# Sheet1.net
KiCad netlist of a schematic drawn in Altium Designer
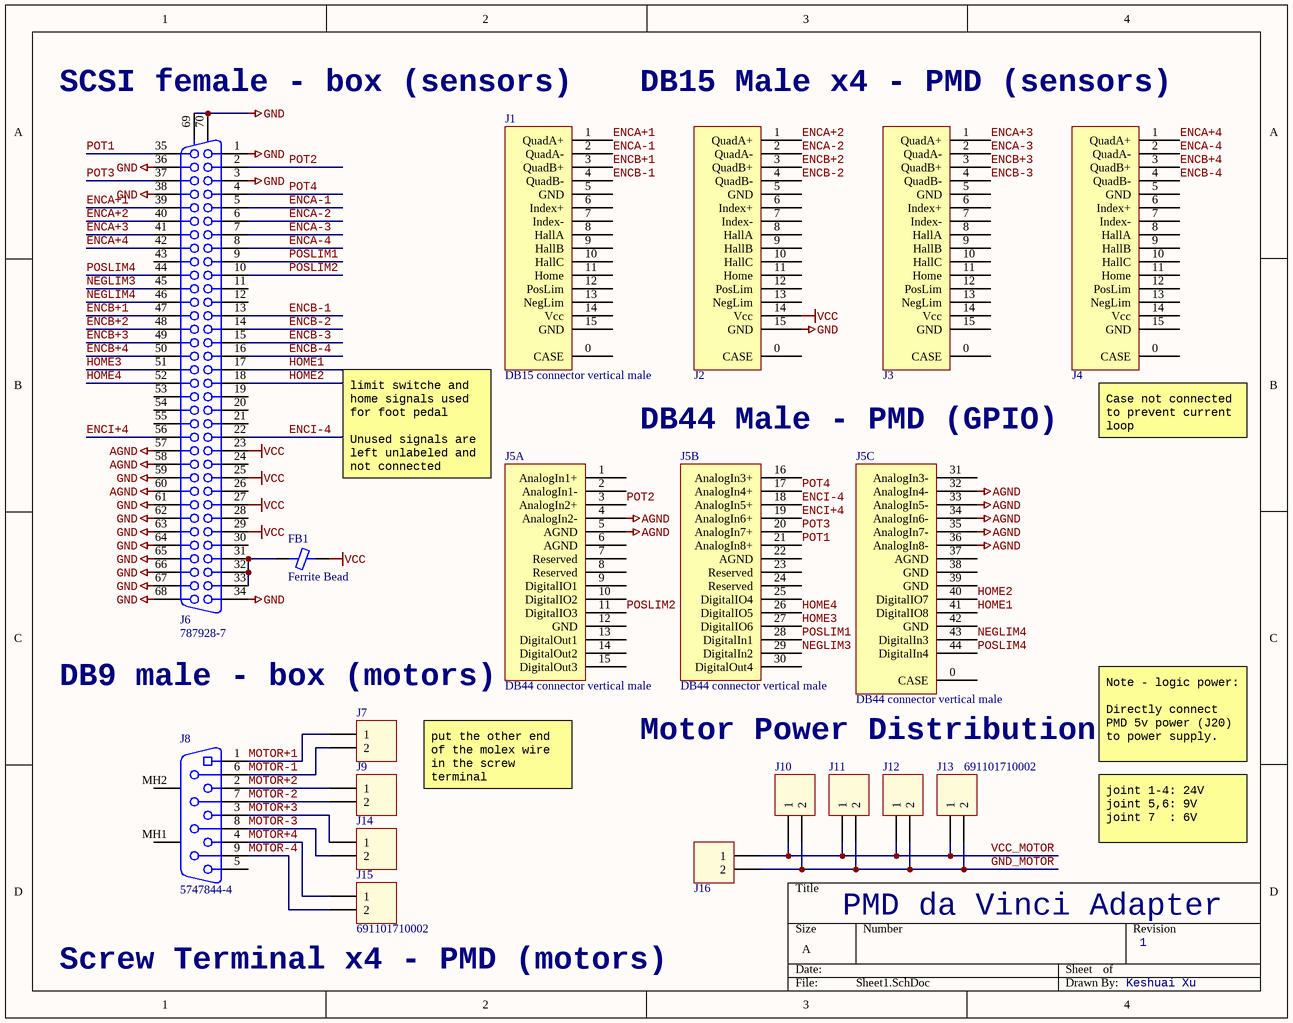
[diagram p0: Sheet1.SchDoc]

(export (version "E")
  (design (tool "Eeschema 10.0.6"))
  (components
    (comp (ref "FB1")
      (value "Ferrite Bead")
      (footprint "IND_0603")
      (description "SMT Ferrite Chip")
      (libsource (lib "Passives") (part "Ferrite Chip"))
    )
    (comp (ref "J1")
      (value "DB15 connector vertical male")
      (footprint "10090928-P154XLF")
      (libsource (lib "pmd_davinci_adapter") (part "PMD-sensor"))
    )
    (comp (ref "J2")
      (value "DB15 connector vertical male")
      (footprint "10090928-P154XLF")
      (libsource (lib "pmd_davinci_adapter") (part "PMD-sensor"))
    )
    (comp (ref "J3")
      (value "DB15 connector vertical male")
      (footprint "10090928-P154XLF")
      (libsource (lib "pmd_davinci_adapter") (part "PMD-sensor"))
    )
    (comp (ref "J4")
      (value "DB15 connector vertical male")
      (footprint "10090928-P154XLF")
      (libsource (lib "pmd_davinci_adapter") (part "PMD-sensor"))
    )
    (comp (ref "J5")
      (value "DB44 connector vertical male")
      (footprint "10090928-P444XLF")
      (libsource (lib "pmd_davinci_adapter") (part "PMD-GPIO"))
    )
    (comp (ref "J6")
      (value "787928-7")
      (footprint "787928-7")
      (description "Receptacle Assembly, Shielded, Right Angle, AMPLIMITE")
      (fields (field (name "PUBLISHER") "Altium Limited"))
      (libsource (lib "pmd_davinci_adapter") (part "787928-7"))
    )
    (comp (ref "J7")
      (value "691101710002")
      (footprint "691101710002")
      (description "WR-TBL Serie 101 - 5.00 mm Horizontal Entry Modular, 02p")
      (fields (field (name "PUBLISHER") "Wurth Elektronik"))
      (libsource (lib "ALTIUM-TBL_5_00_THR_5027_HORIZONTAL_ENTRY_MODULAR_W_PRESSURE_CLAMP_69150271000X-rev17a") (part "691101710002"))
    )
    (comp (ref "J8")
      (value "5747844-4")
      (footprint "TE-5747844-4_V")
      (fields (field (name "MANUFACTURER") "TE Connectivity"))
      (libsource (lib "Altium Content Vault") (part "CN-2S-2F-D9"))
    )
    (comp (ref "J9")
      (value "691101710002")
      (footprint "691101710002")
      (description "WR-TBL Serie 101 - 5.00 mm Horizontal Entry Modular, 02p")
      (fields (field (name "PUBLISHER") "Wurth Elektronik"))
      (libsource (lib "ALTIUM-TBL_5_00_THR_5027_HORIZONTAL_ENTRY_MODULAR_W_PRESSURE_CLAMP_69150271000X-rev17a") (part "691101710002"))
    )
    (comp (ref "J10")
      (value "691101710002")
      (footprint "691101710002")
      (description "WR-TBL Serie 101 - 5.00 mm Horizontal Entry Modular, 02p")
      (fields (field (name "PUBLISHER") "Wurth Elektronik"))
      (libsource (lib "") (part "691101710002_1"))
    )
    (comp (ref "J11")
      (value "691101710002")
      (footprint "691101710002")
      (description "WR-TBL Serie 101 - 5.00 mm Horizontal Entry Modular, 02p")
      (fields (field (name "PUBLISHER") "Wurth Elektronik"))
      (libsource (lib "") (part "691101710002_1"))
    )
    (comp (ref "J12")
      (value "691101710002")
      (footprint "691101710002")
      (description "WR-TBL Serie 101 - 5.00 mm Horizontal Entry Modular, 02p")
      (fields (field (name "PUBLISHER") "Wurth Elektronik"))
      (libsource (lib "") (part "691101710002_1"))
    )
    (comp (ref "J13")
      (value "691101710002")
      (footprint "691101710002")
      (description "WR-TBL Serie 101 - 5.00 mm Horizontal Entry Modular, 02p")
      (fields (field (name "PUBLISHER") "Wurth Elektronik"))
      (libsource (lib "") (part "691101710002_1"))
    )
    (comp (ref "J14")
      (value "691101710002")
      (footprint "691101710002")
      (description "WR-TBL Serie 101 - 5.00 mm Horizontal Entry Modular, 02p")
      (fields (field (name "PUBLISHER") "Wurth Elektronik"))
      (libsource (lib "ALTIUM-TBL_5_00_THR_5027_HORIZONTAL_ENTRY_MODULAR_W_PRESSURE_CLAMP_69150271000X-rev17a") (part "691101710002"))
    )
    (comp (ref "J15")
      (value "691101710002")
      (footprint "691101710002")
      (description "WR-TBL Serie 101 - 5.00 mm Horizontal Entry Modular, 02p")
      (fields (field (name "PUBLISHER") "Wurth Elektronik"))
      (libsource (lib "ALTIUM-TBL_5_00_THR_5027_HORIZONTAL_ENTRY_MODULAR_W_PRESSURE_CLAMP_69150271000X-rev17a") (part "691101710002"))
    )
    (comp (ref "J16")
      (value "691101710002")
      (footprint "691101710002")
      (description "WR-TBL Serie 101 - 5.00 mm Horizontal Entry Modular, 02p")
      (fields (field (name "PUBLISHER") "Wurth Elektronik"))
      (libsource (lib "") (part "691101710002_2"))
    )
  )
  (nets
    (net (code "1") (name "/ENCA+1") (class "Default")
      (node (ref "J1") (pin "1") (pinfunction "QuadA+_1") (pintype "passive"))
      (node (ref "J6") (pin "39") (pinfunction "39_39") (pintype "passive"))
    )
    (net (code "2") (name "/ENCA+2") (class "Default")
      (node (ref "J2") (pin "1") (pinfunction "QuadA+_1") (pintype "passive"))
      (node (ref "J6") (pin "40") (pinfunction "40_40") (pintype "passive"))
    )
    (net (code "3") (name "/ENCA+3") (class "Default")
      (node (ref "J3") (pin "1") (pinfunction "QuadA+_1") (pintype "passive"))
      (node (ref "J6") (pin "41") (pinfunction "41_41") (pintype "passive"))
    )
    (net (code "4") (name "/ENCA+4") (class "Default")
      (node (ref "J4") (pin "1") (pinfunction "QuadA+_1") (pintype "passive"))
      (node (ref "J6") (pin "42") (pinfunction "42_42") (pintype "passive"))
    )
    (net (code "5") (name "/ENCA-1") (class "Default")
      (node (ref "J1") (pin "2") (pinfunction "QuadA-_2") (pintype "passive"))
      (node (ref "J6") (pin "5") (pinfunction "5_5") (pintype "passive"))
    )
    (net (code "6") (name "/ENCA-2") (class "Default")
      (node (ref "J2") (pin "2") (pinfunction "QuadA-_2") (pintype "passive"))
      (node (ref "J6") (pin "6") (pinfunction "6_6") (pintype "passive"))
    )
    (net (code "7") (name "/ENCA-3") (class "Default")
      (node (ref "J3") (pin "2") (pinfunction "QuadA-_2") (pintype "passive"))
      (node (ref "J6") (pin "7") (pinfunction "7_7") (pintype "passive"))
    )
    (net (code "8") (name "/ENCA-4") (class "Default")
      (node (ref "J4") (pin "2") (pinfunction "QuadA-_2") (pintype "passive"))
      (node (ref "J6") (pin "8") (pinfunction "8_8") (pintype "passive"))
    )
    (net (code "9") (name "/ENCB+1") (class "Default")
      (node (ref "J1") (pin "3") (pinfunction "QuadB+_3") (pintype "passive"))
      (node (ref "J6") (pin "47") (pinfunction "47_47") (pintype "passive"))
    )
    (net (code "10") (name "/ENCB+2") (class "Default")
      (node (ref "J2") (pin "3") (pinfunction "QuadB+_3") (pintype "passive"))
      (node (ref "J6") (pin "48") (pinfunction "48_48") (pintype "passive"))
    )
    (net (code "11") (name "/ENCB+3") (class "Default")
      (node (ref "J3") (pin "3") (pinfunction "QuadB+_3") (pintype "passive"))
      (node (ref "J6") (pin "49") (pinfunction "49_49") (pintype "passive"))
    )
    (net (code "12") (name "/ENCB+4") (class "Default")
      (node (ref "J4") (pin "3") (pinfunction "QuadB+_3") (pintype "passive"))
      (node (ref "J6") (pin "50") (pinfunction "50_50") (pintype "passive"))
    )
    (net (code "13") (name "/ENCB-1") (class "Default")
      (node (ref "J1") (pin "4") (pinfunction "QuadB-_4") (pintype "passive"))
      (node (ref "J6") (pin "13") (pinfunction "13_13") (pintype "passive"))
    )
    (net (code "14") (name "/ENCB-2") (class "Default")
      (node (ref "J2") (pin "4") (pinfunction "QuadB-_4") (pintype "passive"))
      (node (ref "J6") (pin "14") (pinfunction "14_14") (pintype "passive"))
    )
    (net (code "15") (name "/ENCB-3") (class "Default")
      (node (ref "J3") (pin "4") (pinfunction "QuadB-_4") (pintype "passive"))
      (node (ref "J6") (pin "15") (pinfunction "15_15") (pintype "passive"))
    )
    (net (code "16") (name "/ENCB-4") (class "Default")
      (node (ref "J4") (pin "4") (pinfunction "QuadB-_4") (pintype "passive"))
      (node (ref "J6") (pin "16") (pinfunction "16_16") (pintype "passive"))
    )
    (net (code "17") (name "/ENCI+4") (class "Default")
      (node (ref "J5") (pin "19") (pinfunction "AnalogIn6+_19") (pintype "passive"))
      (node (ref "J6") (pin "56") (pinfunction "56_56") (pintype "passive"))
    )
    (net (code "18") (name "/ENCI-4") (class "Default")
      (node (ref "J5") (pin "18") (pinfunction "AnalogIn5+_18") (pintype "passive"))
      (node (ref "J6") (pin "22") (pinfunction "22_22") (pintype "passive"))
    )
    (net (code "19") (name "/GND_MOTOR") (class "Default")
      (node (ref "J10") (pin "2") (pinfunction "2_2") (pintype "passive"))
      (node (ref "J11") (pin "2") (pinfunction "2_2") (pintype "passive"))
      (node (ref "J12") (pin "2") (pinfunction "2_2") (pintype "passive"))
      (node (ref "J13") (pin "2") (pinfunction "2_2") (pintype "passive"))
      (node (ref "J16") (pin "2") (pinfunction "2_2") (pintype "passive"))
    )
    (net (code "20") (name "/HOME1") (class "Default")
      (node (ref "J5") (pin "41") (pinfunction "DigitalIO8_41") (pintype "passive"))
      (node (ref "J6") (pin "17") (pinfunction "17_17") (pintype "passive"))
    )
    (net (code "21") (name "/HOME2") (class "Default")
      (node (ref "J5") (pin "40") (pinfunction "DigitalIO7_40") (pintype "passive"))
      (node (ref "J6") (pin "18") (pinfunction "18_18") (pintype "passive"))
    )
    (net (code "22") (name "/HOME3") (class "Default")
      (node (ref "J5") (pin "27") (pinfunction "DigitalIO6_27") (pintype "passive"))
      (node (ref "J6") (pin "51") (pinfunction "51_51") (pintype "passive"))
    )
    (net (code "23") (name "/HOME4") (class "Default")
      (node (ref "J5") (pin "26") (pinfunction "DigitalIO5_26") (pintype "passive"))
      (node (ref "J6") (pin "52") (pinfunction "52_52") (pintype "passive"))
    )
    (net (code "24") (name "/MOTOR+1") (class "Default")
      (node (ref "J7") (pin "1") (pinfunction "1_1") (pintype "passive"))
      (node (ref "J8") (pin "1") (pinfunction "1_1") (pintype "passive"))
    )
    (net (code "25") (name "/MOTOR+2") (class "Default")
      (node (ref "J8") (pin "2") (pinfunction "2_2") (pintype "passive"))
      (node (ref "J9") (pin "1") (pinfunction "1_1") (pintype "passive"))
    )
    (net (code "26") (name "/MOTOR+3") (class "Default")
      (node (ref "J14") (pin "1") (pinfunction "1_1") (pintype "passive"))
      (node (ref "J8") (pin "3") (pinfunction "3_3") (pintype "passive"))
    )
    (net (code "27") (name "/MOTOR+4") (class "Default")
      (node (ref "J15") (pin "1") (pinfunction "1_1") (pintype "passive"))
      (node (ref "J8") (pin "4") (pinfunction "4_4") (pintype "passive"))
    )
    (net (code "28") (name "/MOTOR-1") (class "Default")
      (node (ref "J7") (pin "2") (pinfunction "2_2") (pintype "passive"))
      (node (ref "J8") (pin "6") (pinfunction "6_6") (pintype "passive"))
    )
    (net (code "29") (name "/MOTOR-2") (class "Default")
      (node (ref "J8") (pin "7") (pinfunction "7_7") (pintype "passive"))
      (node (ref "J9") (pin "2") (pinfunction "2_2") (pintype "passive"))
    )
    (net (code "30") (name "/MOTOR-3") (class "Default")
      (node (ref "J14") (pin "2") (pinfunction "2_2") (pintype "passive"))
      (node (ref "J8") (pin "8") (pinfunction "8_8") (pintype "passive"))
    )
    (net (code "31") (name "/MOTOR-4") (class "Default")
      (node (ref "J15") (pin "2") (pinfunction "2_2") (pintype "passive"))
      (node (ref "J8") (pin "9") (pinfunction "9_9") (pintype "passive"))
    )
    (net (code "32") (name "/NEGLIM3") (class "Default")
      (node (ref "J5") (pin "29") (pinfunction "DigitalIn2_29") (pintype "passive"))
      (node (ref "J6") (pin "45") (pinfunction "45_45") (pintype "passive"))
    )
    (net (code "33") (name "/NEGLIM4") (class "Default")
      (node (ref "J5") (pin "43") (pinfunction "DigitalIn3_43") (pintype "passive"))
      (node (ref "J6") (pin "46") (pinfunction "46_46") (pintype "passive"))
    )
    (net (code "34") (name "/POSLIM1") (class "Default")
      (node (ref "J5") (pin "28") (pinfunction "DigitalIn1_28") (pintype "passive"))
      (node (ref "J6") (pin "9") (pinfunction "9_9") (pintype "passive"))
    )
    (net (code "35") (name "/POSLIM2") (class "Default")
      (node (ref "J5") (pin "11") (pinfunction "DigitalIO3_11") (pintype "passive"))
      (node (ref "J6") (pin "10") (pinfunction "10_10") (pintype "passive"))
    )
    (net (code "36") (name "/POSLIM4") (class "Default")
      (node (ref "J5") (pin "44") (pinfunction "DigitalIn4_44") (pintype "passive"))
      (node (ref "J6") (pin "44") (pinfunction "44_44") (pintype "passive"))
    )
    (net (code "37") (name "/POT1") (class "Default")
      (node (ref "J5") (pin "21") (pinfunction "AnalogIn8+_21") (pintype "passive"))
      (node (ref "J6") (pin "35") (pinfunction "35_35") (pintype "passive"))
    )
    (net (code "38") (name "/POT2") (class "Default")
      (node (ref "J5") (pin "3") (pinfunction "AnalogIn2+_3") (pintype "passive"))
      (node (ref "J6") (pin "2") (pinfunction "2_2") (pintype "passive"))
    )
    (net (code "39") (name "/POT3") (class "Default")
      (node (ref "J5") (pin "20") (pinfunction "AnalogIn7+_20") (pintype "passive"))
      (node (ref "J6") (pin "37") (pinfunction "37_37") (pintype "passive"))
    )
    (net (code "40") (name "/POT4") (class "Default")
      (node (ref "J5") (pin "17") (pinfunction "AnalogIn4+_17") (pintype "passive"))
      (node (ref "J6") (pin "4") (pinfunction "4_4") (pintype "passive"))
    )
    (net (code "41") (name "/VCC_MOTOR") (class "Default")
      (node (ref "J10") (pin "1") (pinfunction "1_1") (pintype "passive"))
      (node (ref "J11") (pin "1") (pinfunction "1_1") (pintype "passive"))
      (node (ref "J12") (pin "1") (pinfunction "1_1") (pintype "passive"))
      (node (ref "J13") (pin "1") (pinfunction "1_1") (pintype "passive"))
      (node (ref "J16") (pin "1") (pinfunction "1_1") (pintype "passive"))
    )
    (net (code "42") (name "AGND") (class "Default")
      (node (ref "J5") (pin "32") (pinfunction "AnalogIn4-_32") (pintype "passive"))
      (node (ref "J5") (pin "33") (pinfunction "AnalogIn5-_33") (pintype "passive"))
      (node (ref "J5") (pin "34") (pinfunction "AnalogIn6-_34") (pintype "passive"))
      (node (ref "J5") (pin "35") (pinfunction "AnalogIn7-_35") (pintype "passive"))
      (node (ref "J5") (pin "36") (pinfunction "AnalogIn8-_36") (pintype "passive"))
      (node (ref "J5") (pin "4") (pinfunction "AnalogIn2-_4") (pintype "passive"))
      (node (ref "J5") (pin "5") (pinfunction "AGND_5") (pintype "passive"))
      (node (ref "J6") (pin "57") (pinfunction "57_57") (pintype "passive"))
      (node (ref "J6") (pin "58") (pinfunction "58_58") (pintype "passive"))
      (node (ref "J6") (pin "60") (pinfunction "60_60") (pintype "passive"))
    )
    (net (code "43") (name "GND") (class "Default")
      (node (ref "J2") (pin "15") (pinfunction "GND_15") (pintype "passive"))
      (node (ref "J6") (pin "1") (pinfunction "1_1") (pintype "passive"))
      (node (ref "J6") (pin "3") (pinfunction "3_3") (pintype "passive"))
      (node (ref "J6") (pin "34") (pinfunction "34_34") (pintype "passive"))
      (node (ref "J6") (pin "36") (pinfunction "36_36") (pintype "passive"))
      (node (ref "J6") (pin "38") (pinfunction "38_38") (pintype "passive"))
      (node (ref "J6") (pin "59") (pinfunction "59_59") (pintype "passive"))
      (node (ref "J6") (pin "61") (pinfunction "61_61") (pintype "passive"))
      (node (ref "J6") (pin "62") (pinfunction "62_62") (pintype "passive"))
      (node (ref "J6") (pin "63") (pinfunction "63_63") (pintype "passive"))
      (node (ref "J6") (pin "64") (pinfunction "64_64") (pintype "passive"))
      (node (ref "J6") (pin "65") (pinfunction "65_65") (pintype "passive"))
      (node (ref "J6") (pin "66") (pinfunction "66_66") (pintype "passive"))
      (node (ref "J6") (pin "67") (pinfunction "67_67") (pintype "passive"))
      (node (ref "J6") (pin "68") (pinfunction "68_68") (pintype "passive"))
      (node (ref "J6") (pin "69") (pinfunction "MH1_69") (pintype "passive"))
      (node (ref "J6") (pin "70") (pinfunction "MH2_70") (pintype "passive"))
    )
    (net (code "44") (name "Net-(FB1-Pad1)") (class "Default")
      (node (ref "FB1") (pin "1") (pinfunction "1_1") (pintype "passive"))
      (node (ref "J6") (pin "31") (pinfunction "31_31") (pintype "passive"))
      (node (ref "J6") (pin "32") (pinfunction "32_32") (pintype "passive"))
      (node (ref "J6") (pin "33") (pinfunction "33_33") (pintype "passive"))
    )
    (net (code "45") (name "VCC") (class "Default")
      (node (ref "FB1") (pin "2") (pinfunction "2_2") (pintype "passive"))
      (node (ref "J2") (pin "14") (pinfunction "Vcc_14") (pintype "passive"))
      (node (ref "J6") (pin "23") (pinfunction "23_23") (pintype "passive"))
      (node (ref "J6") (pin "25") (pinfunction "25_25") (pintype "passive"))
      (node (ref "J6") (pin "27") (pinfunction "27_27") (pintype "passive"))
      (node (ref "J6") (pin "29") (pinfunction "29_29") (pintype "passive"))
    )
    (net (code "46") (name "unconnected-(J1-CASE-Pad0)") (class "Default")
      (node (ref "J1") (pin "0") (pinfunction "CASE_0") (pintype "passive"))
    )
    (net (code "47") (name "unconnected-(J1-GND-Pad5)") (class "Default")
      (node (ref "J1") (pin "5") (pinfunction "GND_5") (pintype "passive"))
    )
    (net (code "48") (name "unconnected-(J1-GND-Pad15)") (class "Default")
      (node (ref "J1") (pin "15") (pinfunction "GND_15") (pintype "passive"))
    )
    (net (code "49") (name "unconnected-(J1-HallA-Pad8)") (class "Default")
      (node (ref "J1") (pin "8") (pinfunction "HallA_8") (pintype "passive"))
    )
    (net (code "50") (name "unconnected-(J1-HallB-Pad9)") (class "Default")
      (node (ref "J1") (pin "9") (pinfunction "HallB_9") (pintype "passive"))
    )
    (net (code "51") (name "unconnected-(J1-HallC-Pad10)") (class "Default")
      (node (ref "J1") (pin "10") (pinfunction "HallC_10") (pintype "passive"))
    )
    (net (code "52") (name "unconnected-(J1-Home-Pad11)") (class "Default")
      (node (ref "J1") (pin "11") (pinfunction "Home_11") (pintype "passive"))
    )
    (net (code "53") (name "unconnected-(J1-Index+-Pad6)") (class "Default")
      (node (ref "J1") (pin "6") (pinfunction "Index+_6") (pintype "passive"))
    )
    (net (code "54") (name "unconnected-(J1-Index--Pad7)") (class "Default")
      (node (ref "J1") (pin "7") (pinfunction "Index-_7") (pintype "passive"))
    )
    (net (code "55") (name "unconnected-(J1-NegLim-Pad13)") (class "Default")
      (node (ref "J1") (pin "13") (pinfunction "NegLim_13") (pintype "passive"))
    )
    (net (code "56") (name "unconnected-(J1-PosLim-Pad12)") (class "Default")
      (node (ref "J1") (pin "12") (pinfunction "PosLim_12") (pintype "passive"))
    )
    (net (code "57") (name "unconnected-(J1-Vcc-Pad14)") (class "Default")
      (node (ref "J1") (pin "14") (pinfunction "Vcc_14") (pintype "passive"))
    )
    (net (code "58") (name "unconnected-(J2-CASE-Pad0)") (class "Default")
      (node (ref "J2") (pin "0") (pinfunction "CASE_0") (pintype "passive"))
    )
    (net (code "59") (name "unconnected-(J2-GND-Pad5)") (class "Default")
      (node (ref "J2") (pin "5") (pinfunction "GND_5") (pintype "passive"))
    )
    (net (code "60") (name "unconnected-(J2-HallA-Pad8)") (class "Default")
      (node (ref "J2") (pin "8") (pinfunction "HallA_8") (pintype "passive"))
    )
    (net (code "61") (name "unconnected-(J2-HallB-Pad9)") (class "Default")
      (node (ref "J2") (pin "9") (pinfunction "HallB_9") (pintype "passive"))
    )
    (net (code "62") (name "unconnected-(J2-HallC-Pad10)") (class "Default")
      (node (ref "J2") (pin "10") (pinfunction "HallC_10") (pintype "passive"))
    )
    (net (code "63") (name "unconnected-(J2-Home-Pad11)") (class "Default")
      (node (ref "J2") (pin "11") (pinfunction "Home_11") (pintype "passive"))
    )
    (net (code "64") (name "unconnected-(J2-Index+-Pad6)") (class "Default")
      (node (ref "J2") (pin "6") (pinfunction "Index+_6") (pintype "passive"))
    )
    (net (code "65") (name "unconnected-(J2-Index--Pad7)") (class "Default")
      (node (ref "J2") (pin "7") (pinfunction "Index-_7") (pintype "passive"))
    )
    (net (code "66") (name "unconnected-(J2-NegLim-Pad13)") (class "Default")
      (node (ref "J2") (pin "13") (pinfunction "NegLim_13") (pintype "passive"))
    )
    (net (code "67") (name "unconnected-(J2-PosLim-Pad12)") (class "Default")
      (node (ref "J2") (pin "12") (pinfunction "PosLim_12") (pintype "passive"))
    )
    (net (code "68") (name "unconnected-(J3-CASE-Pad0)") (class "Default")
      (node (ref "J3") (pin "0") (pinfunction "CASE_0") (pintype "passive"))
    )
    (net (code "69") (name "unconnected-(J3-GND-Pad5)") (class "Default")
      (node (ref "J3") (pin "5") (pinfunction "GND_5") (pintype "passive"))
    )
    (net (code "70") (name "unconnected-(J3-GND-Pad15)") (class "Default")
      (node (ref "J3") (pin "15") (pinfunction "GND_15") (pintype "passive"))
    )
    (net (code "71") (name "unconnected-(J3-HallA-Pad8)") (class "Default")
      (node (ref "J3") (pin "8") (pinfunction "HallA_8") (pintype "passive"))
    )
    (net (code "72") (name "unconnected-(J3-HallB-Pad9)") (class "Default")
      (node (ref "J3") (pin "9") (pinfunction "HallB_9") (pintype "passive"))
    )
    (net (code "73") (name "unconnected-(J3-HallC-Pad10)") (class "Default")
      (node (ref "J3") (pin "10") (pinfunction "HallC_10") (pintype "passive"))
    )
    (net (code "74") (name "unconnected-(J3-Home-Pad11)") (class "Default")
      (node (ref "J3") (pin "11") (pinfunction "Home_11") (pintype "passive"))
    )
    (net (code "75") (name "unconnected-(J3-Index+-Pad6)") (class "Default")
      (node (ref "J3") (pin "6") (pinfunction "Index+_6") (pintype "passive"))
    )
    (net (code "76") (name "unconnected-(J3-Index--Pad7)") (class "Default")
      (node (ref "J3") (pin "7") (pinfunction "Index-_7") (pintype "passive"))
    )
    (net (code "77") (name "unconnected-(J3-NegLim-Pad13)") (class "Default")
      (node (ref "J3") (pin "13") (pinfunction "NegLim_13") (pintype "passive"))
    )
    (net (code "78") (name "unconnected-(J3-PosLim-Pad12)") (class "Default")
      (node (ref "J3") (pin "12") (pinfunction "PosLim_12") (pintype "passive"))
    )
    (net (code "79") (name "unconnected-(J3-Vcc-Pad14)") (class "Default")
      (node (ref "J3") (pin "14") (pinfunction "Vcc_14") (pintype "passive"))
    )
    (net (code "80") (name "unconnected-(J4-CASE-Pad0)") (class "Default")
      (node (ref "J4") (pin "0") (pinfunction "CASE_0") (pintype "passive"))
    )
    (net (code "81") (name "unconnected-(J4-GND-Pad5)") (class "Default")
      (node (ref "J4") (pin "5") (pinfunction "GND_5") (pintype "passive"))
    )
    (net (code "82") (name "unconnected-(J4-GND-Pad15)") (class "Default")
      (node (ref "J4") (pin "15") (pinfunction "GND_15") (pintype "passive"))
    )
    (net (code "83") (name "unconnected-(J4-HallA-Pad8)") (class "Default")
      (node (ref "J4") (pin "8") (pinfunction "HallA_8") (pintype "passive"))
    )
    (net (code "84") (name "unconnected-(J4-HallB-Pad9)") (class "Default")
      (node (ref "J4") (pin "9") (pinfunction "HallB_9") (pintype "passive"))
    )
    (net (code "85") (name "unconnected-(J4-HallC-Pad10)") (class "Default")
      (node (ref "J4") (pin "10") (pinfunction "HallC_10") (pintype "passive"))
    )
    (net (code "86") (name "unconnected-(J4-Home-Pad11)") (class "Default")
      (node (ref "J4") (pin "11") (pinfunction "Home_11") (pintype "passive"))
    )
    (net (code "87") (name "unconnected-(J4-Index+-Pad6)") (class "Default")
      (node (ref "J4") (pin "6") (pinfunction "Index+_6") (pintype "passive"))
    )
    (net (code "88") (name "unconnected-(J4-Index--Pad7)") (class "Default")
      (node (ref "J4") (pin "7") (pinfunction "Index-_7") (pintype "passive"))
    )
    (net (code "89") (name "unconnected-(J4-NegLim-Pad13)") (class "Default")
      (node (ref "J4") (pin "13") (pinfunction "NegLim_13") (pintype "passive"))
    )
    (net (code "90") (name "unconnected-(J4-PosLim-Pad12)") (class "Default")
      (node (ref "J4") (pin "12") (pinfunction "PosLim_12") (pintype "passive"))
    )
    (net (code "91") (name "unconnected-(J4-Vcc-Pad14)") (class "Default")
      (node (ref "J4") (pin "14") (pinfunction "Vcc_14") (pintype "passive"))
    )
    (net (code "92") (name "unconnected-(J5A-AGND-Pad6)") (class "Default")
      (node (ref "J5") (pin "6") (pinfunction "AGND_6") (pintype "passive"))
    )
    (net (code "93") (name "unconnected-(J5A-AnalogIn1+-Pad1)") (class "Default")
      (node (ref "J5") (pin "1") (pinfunction "AnalogIn1+_1") (pintype "passive"))
    )
    (net (code "94") (name "unconnected-(J5A-AnalogIn1--Pad2)") (class "Default")
      (node (ref "J5") (pin "2") (pinfunction "AnalogIn1-_2") (pintype "passive"))
    )
    (net (code "95") (name "unconnected-(J5A-DigitalIO1-Pad9)") (class "Default")
      (node (ref "J5") (pin "9") (pinfunction "DigitalIO1_9") (pintype "passive"))
    )
    (net (code "96") (name "unconnected-(J5A-DigitalIO2-Pad10)") (class "Default")
      (node (ref "J5") (pin "10") (pinfunction "DigitalIO2_10") (pintype "passive"))
    )
    (net (code "97") (name "unconnected-(J5A-DigitalOut1-Pad13)") (class "Default")
      (node (ref "J5") (pin "13") (pinfunction "DigitalOut1_13") (pintype "passive"))
    )
    (net (code "98") (name "unconnected-(J5A-DigitalOut2-Pad14)") (class "Default")
      (node (ref "J5") (pin "14") (pinfunction "DigitalOut2_14") (pintype "passive"))
    )
    (net (code "99") (name "unconnected-(J5A-DigitalOut3-Pad15)") (class "Default")
      (node (ref "J5") (pin "15") (pinfunction "DigitalOut3_15") (pintype "passive"))
    )
    (net (code "100") (name "unconnected-(J5A-GND-Pad12)") (class "Default")
      (node (ref "J5") (pin "12") (pinfunction "GND_12") (pintype "passive"))
    )
    (net (code "101") (name "unconnected-(J5A-Reserved-Pad7)") (class "Default")
      (node (ref "J5") (pin "7") (pinfunction "Reserved_7") (pintype "passive"))
    )
    (net (code "102") (name "unconnected-(J5A-Reserved-Pad8)") (class "Default")
      (node (ref "J5") (pin "8") (pinfunction "Reserved_8") (pintype "passive"))
    )
    (net (code "103") (name "unconnected-(J5B-AGND-Pad22)") (class "Default")
      (node (ref "J5") (pin "22") (pinfunction "AGND_22") (pintype "passive"))
    )
    (net (code "104") (name "unconnected-(J5B-AnalogIn3+-Pad16)") (class "Default")
      (node (ref "J5") (pin "16") (pinfunction "AnalogIn3+_16") (pintype "passive"))
    )
    (net (code "105") (name "unconnected-(J5B-DigitalIO4-Pad25)") (class "Default")
      (node (ref "J5") (pin "25") (pinfunction "DigitalIO4_25") (pintype "passive"))
    )
    (net (code "106") (name "unconnected-(J5B-DigitalOut4-Pad30)") (class "Default")
      (node (ref "J5") (pin "30") (pinfunction "DigitalOut4_30") (pintype "passive"))
    )
    (net (code "107") (name "unconnected-(J5B-Reserved-Pad23)") (class "Default")
      (node (ref "J5") (pin "23") (pinfunction "Reserved_23") (pintype "passive"))
    )
    (net (code "108") (name "unconnected-(J5B-Reserved-Pad24)") (class "Default")
      (node (ref "J5") (pin "24") (pinfunction "Reserved_24") (pintype "passive"))
    )
    (net (code "109") (name "unconnected-(J5C-AGND-Pad37)") (class "Default")
      (node (ref "J5") (pin "37") (pinfunction "AGND_37") (pintype "passive"))
    )
    (net (code "110") (name "unconnected-(J5C-AnalogIn3--Pad31)") (class "Default")
      (node (ref "J5") (pin "31") (pinfunction "AnalogIn3-_31") (pintype "passive"))
    )
    (net (code "111") (name "unconnected-(J5C-CASE-Pad0)") (class "Default")
      (node (ref "J5") (pin "0") (pinfunction "CASE_0") (pintype "passive"))
    )
    (net (code "112") (name "unconnected-(J5C-GND-Pad38)") (class "Default")
      (node (ref "J5") (pin "38") (pinfunction "GND_38") (pintype "passive"))
    )
    (net (code "113") (name "unconnected-(J5C-GND-Pad39)") (class "Default")
      (node (ref "J5") (pin "39") (pinfunction "GND_39") (pintype "passive"))
    )
    (net (code "114") (name "unconnected-(J5C-GND-Pad42)") (class "Default")
      (node (ref "J5") (pin "42") (pinfunction "GND_42") (pintype "passive"))
    )
    (net (code "115") (name "unconnected-(J6-Pad11)") (class "Default")
      (node (ref "J6") (pin "11") (pinfunction "11_11") (pintype "passive"))
    )
    (net (code "116") (name "unconnected-(J6-Pad12)") (class "Default")
      (node (ref "J6") (pin "12") (pinfunction "12_12") (pintype "passive"))
    )
    (net (code "117") (name "unconnected-(J6-Pad19)") (class "Default")
      (node (ref "J6") (pin "19") (pinfunction "19_19") (pintype "passive"))
    )
    (net (code "118") (name "unconnected-(J6-Pad20)") (class "Default")
      (node (ref "J6") (pin "20") (pinfunction "20_20") (pintype "passive"))
    )
    (net (code "119") (name "unconnected-(J6-Pad21)") (class "Default")
      (node (ref "J6") (pin "21") (pinfunction "21_21") (pintype "passive"))
    )
    (net (code "120") (name "unconnected-(J6-Pad24)") (class "Default")
      (node (ref "J6") (pin "24") (pinfunction "24_24") (pintype "passive"))
    )
    (net (code "121") (name "unconnected-(J6-Pad26)") (class "Default")
      (node (ref "J6") (pin "26") (pinfunction "26_26") (pintype "passive"))
    )
    (net (code "122") (name "unconnected-(J6-Pad28)") (class "Default")
      (node (ref "J6") (pin "28") (pinfunction "28_28") (pintype "passive"))
    )
    (net (code "123") (name "unconnected-(J6-Pad30)") (class "Default")
      (node (ref "J6") (pin "30") (pinfunction "30_30") (pintype "passive"))
    )
    (net (code "124") (name "unconnected-(J6-Pad43)") (class "Default")
      (node (ref "J6") (pin "43") (pinfunction "43_43") (pintype "passive"))
    )
    (net (code "125") (name "unconnected-(J6-Pad53)") (class "Default")
      (node (ref "J6") (pin "53") (pinfunction "53_53") (pintype "passive"))
    )
    (net (code "126") (name "unconnected-(J6-Pad54)") (class "Default")
      (node (ref "J6") (pin "54") (pinfunction "54_54") (pintype "passive"))
    )
    (net (code "127") (name "unconnected-(J6-Pad55)") (class "Default")
      (node (ref "J6") (pin "55") (pinfunction "55_55") (pintype "passive"))
    )
    (net (code "128") (name "unconnected-(J8-Pad5)") (class "Default")
      (node (ref "J8") (pin "5") (pinfunction "5_5") (pintype "passive"))
    )
    (net (code "129") (name "unconnected-(J8-PadMH1)") (class "Default")
      (node (ref "J8") (pin "MH1") (pinfunction "MH1_MH1") (pintype "passive"))
    )
    (net (code "130") (name "unconnected-(J8-PadMH2)") (class "Default")
      (node (ref "J8") (pin "MH2") (pinfunction "MH2_MH2") (pintype "passive"))
    )
  )
)
